# 6x4.net
KiCad netlist of a schematic drawn in Altium Designer
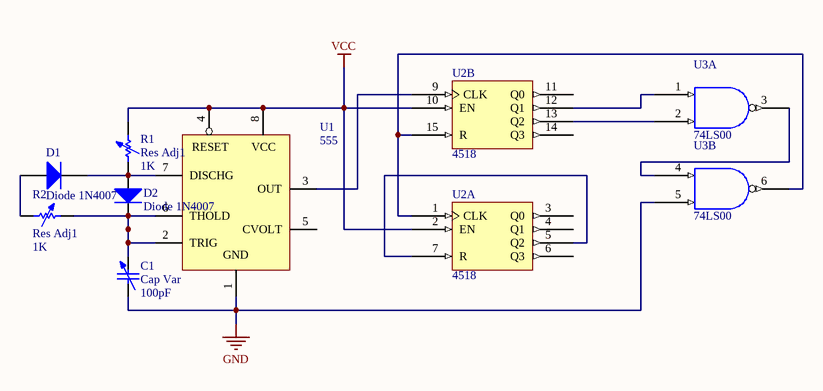
[diagram p0: 6x4.SchDoc]

(export (version "E")
  (design (tool "Eeschema 10.0.6"))
  (components
    (comp (ref "C1")
      (value "Cap Var")
      (footprint "C1210_N")
      (description "Variable or Adjustable Capacitor")
      (fields (field (name "ALTIUM_VALUE") "100pF") (field (name "PUBLISHER") "Altium Limited"))
      (libsource (lib "Miscellaneous Devices") (part "Cap Var"))
    )
    (comp (ref "D1")
      (value "Diode 1N4007")
      (footprint "DO-41")
      (description "1 Amp General Purpose Rectifier")
      (fields (field (name "PUBLISHER") "Altium Limited"))
      (libsource (lib "Miscellaneous Devices") (part "Diode 1N4007"))
    )
    (comp (ref "D2")
      (value "Diode 1N4007")
      (footprint "DO-41")
      (description "1 Amp General Purpose Rectifier")
      (fields (field (name "PUBLISHER") "Altium Limited"))
      (libsource (lib "Miscellaneous Devices") (part "Diode 1N4007"))
    )
    (comp (ref "R1")
      (value "Res Adj1")
      (footprint "AXIAL-0.7")
      (description "Variable Resistor")
      (fields (field (name "ALTIUM_VALUE") "1K") (field (name "PUBLISHER") "Altium Limited"))
      (libsource (lib "Miscellaneous Devices") (part "Res Adj1"))
    )
    (comp (ref "R2")
      (value "Res Adj1")
      (footprint "AXIAL-0.7")
      (description "Variable Resistor")
      (fields (field (name "ALTIUM_VALUE") "1K") (field (name "PUBLISHER") "Altium Limited"))
      (libsource (lib "Miscellaneous Devices") (part "Res Adj1"))
    )
    (comp (ref "U1") (value "555") (description "Timer") (libsource (lib "555") (part "555")))
    (comp (ref "U2") (value "4518") (footprint "DIP-16") (libsource (lib "CD4000系列IC") (part "4518")))
    (comp (ref "U3") (value "74LS00") (footprint "DIP-14") (libsource (lib "TTL74系列IC") (part "74LS00")))
  )
  (nets
    (net (code "1") (name "GND") (class "Default")
      (node (ref "C1") (pin "1") (pinfunction "1_1") (pintype "passive"))
      (node (ref "U1") (pin "1") (pinfunction "GND_1") (pintype "passive"))
      (node (ref "U2") (pin "8") (pinfunction "GND_8") (pintype "power_in"))
      (node (ref "U3") (pin "5") (pintype "input"))
      (node (ref "U3") (pin "7") (pinfunction "GND_7") (pintype "power_in"))
    )
    (net (code "2") (name "Net-(D1-A)") (class "Default")
      (node (ref "D1") (pin "1") (pinfunction "A_1") (pintype "passive"))
      (node (ref "R2") (pin "1") (pinfunction "1_1") (pintype "passive"))
    )
    (net (code "3") (name "Net-(D1-K)") (class "Default")
      (node (ref "D1") (pin "2") (pinfunction "K_2") (pintype "passive"))
      (node (ref "R1") (pin "1") (pinfunction "1_1") (pintype "passive"))
      (node (ref "U1") (pin "7") (pinfunction "DISCHG_7") (pintype "passive"))
    )
    (net (code "4") (name "Net-(D2-K)") (class "Default")
      (node (ref "C1") (pin "2") (pinfunction "2_2") (pintype "passive"))
      (node (ref "D2") (pin "2") (pinfunction "K_2") (pintype "passive"))
      (node (ref "R2") (pin "2") (pinfunction "2_2") (pintype "passive"))
      (node (ref "U1") (pin "2") (pinfunction "TRIG_2") (pintype "passive"))
      (node (ref "U1") (pin "6") (pinfunction "THOLD_6") (pintype "passive"))
    )
    (net (code "5") (name "Net-(U1-OUT)") (class "Default")
      (node (ref "U1") (pin "3") (pinfunction "OUT_3") (pintype "passive"))
      (node (ref "U2") (pin "9") (pinfunction "CLK_9") (pintype "input"))
    )
    (net (code "6") (name "Net-(U2A-CLK)") (class "Default")
      (node (ref "U2") (pin "1") (pinfunction "CLK_1") (pintype "input"))
      (node (ref "U2") (pin "15") (pinfunction "R_15") (pintype "input"))
      (node (ref "U3") (pin "6") (pintype "output"))
    )
    (net (code "7") (name "Net-(U2A-Q2)") (class "Default")
      (node (ref "U2") (pin "5") (pinfunction "Q2_5") (pintype "output"))
      (node (ref "U2") (pin "7") (pinfunction "R_7") (pintype "input"))
    )
    (net (code "8") (name "Net-(U2B-Q1)") (class "Default")
      (node (ref "U2") (pin "12") (pinfunction "Q1_12") (pintype "output"))
      (node (ref "U3") (pin "1") (pintype "input"))
    )
    (net (code "9") (name "Net-(U2B-Q2)") (class "Default")
      (node (ref "U2") (pin "13") (pinfunction "Q2_13") (pintype "output"))
      (node (ref "U3") (pin "2") (pintype "input"))
    )
    (net (code "10") (name "Net-(U3-Pad3)") (class "Default")
      (node (ref "U3") (pin "3") (pintype "output"))
      (node (ref "U3") (pin "4") (pintype "input"))
    )
    (net (code "11") (name "VCC") (class "Default")
      (node (ref "R1") (pin "2") (pinfunction "2_2") (pintype "passive"))
      (node (ref "U1") (pin "4") (pinfunction "RESET_4") (pintype "passive"))
      (node (ref "U1") (pin "8") (pinfunction "VCC_8") (pintype "passive"))
      (node (ref "U2") (pin "10") (pinfunction "EN_10") (pintype "input"))
      (node (ref "U2") (pin "16") (pinfunction "VCC_16") (pintype "power_in"))
      (node (ref "U2") (pin "2") (pinfunction "EN_2") (pintype "input"))
      (node (ref "U3") (pin "14") (pinfunction "VCC_14") (pintype "power_in"))
    )
    (net (code "12") (name "unconnected-(D2-A-Pad1)") (class "Default")
      (node (ref "D2") (pin "1") (pinfunction "A_1") (pintype "passive"))
    )
    (net (code "13") (name "unconnected-(U1-CVOLT-Pad5)") (class "Default")
      (node (ref "U1") (pin "5") (pinfunction "CVOLT_5") (pintype "passive"))
    )
    (net (code "14") (name "unconnected-(U2A-Q0-Pad3)") (class "Default")
      (node (ref "U2") (pin "3") (pinfunction "Q0_3") (pintype "output"))
    )
    (net (code "15") (name "unconnected-(U2A-Q1-Pad4)") (class "Default")
      (node (ref "U2") (pin "4") (pinfunction "Q1_4") (pintype "output"))
    )
    (net (code "16") (name "unconnected-(U2A-Q3-Pad6)") (class "Default")
      (node (ref "U2") (pin "6") (pinfunction "Q3_6") (pintype "output"))
    )
    (net (code "17") (name "unconnected-(U2B-Q0-Pad11)") (class "Default")
      (node (ref "U2") (pin "11") (pinfunction "Q0_11") (pintype "output"))
    )
    (net (code "18") (name "unconnected-(U2B-Q3-Pad14)") (class "Default")
      (node (ref "U2") (pin "14") (pinfunction "Q3_14") (pintype "output"))
    )
  )
)
